# PK_MUV_L2.net
KiCad netlist of a schematic drawn in EAGLE
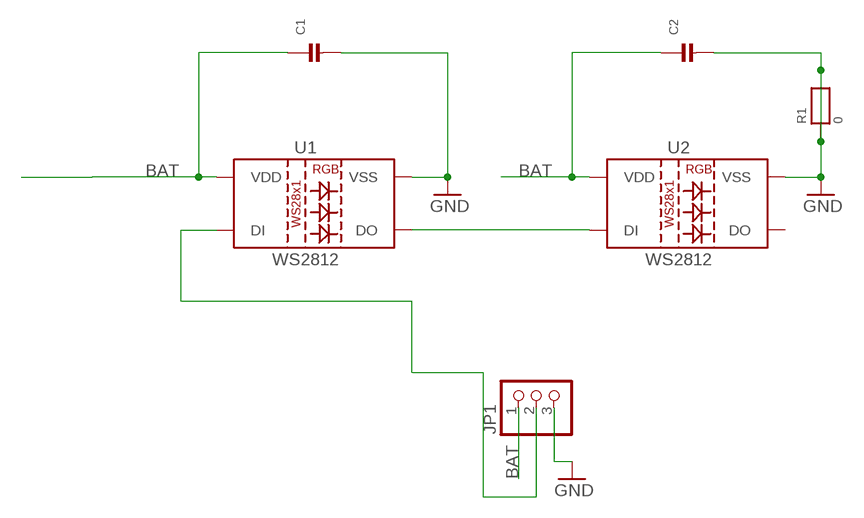
[diagram p0: schematic, sheet 1]

(export (version "E")
  (design (tool "Eeschema 10.0.6"))
  (components
    (comp (ref "C1")
      (value "CAP_CERAMIC1206")
      (footprint "eagle-import:1206")
      (libsource (lib "eagle-import") (part "CAP_CERAMIC1206"))
    )
    (comp (ref "C2")
      (value "CAP_CERAMIC1206")
      (footprint "eagle-import:1206")
      (libsource (lib "eagle-import") (part "CAP_CERAMIC1206"))
    )
    (comp (ref "JP1")
      (value "HEADER-1X3")
      (footprint "eagle-import:1X03_OVAL")
      (libsource (lib "eagle-import") (part "HEADER-1X3"))
    )
    (comp (ref "R1")
      (value "0")
      (footprint "eagle-import:1206")
      (libsource (lib "eagle-import") (part "RESISTOR1206"))
    )
    (comp (ref "U1")
      (value "WS2812")
      (footprint "eagle-import:LED-TRICOLOR-5050-IC")
      (libsource (lib "eagle-import") (part "WS2812{dblquote}"))
    )
    (comp (ref "U2")
      (value "WS2812")
      (footprint "eagle-import:LED-TRICOLOR-5050-IC")
      (libsource (lib "eagle-import") (part "WS2812{dblquote}"))
    )
  )
  (nets
    (net (code "1") (name "/BAT") (class "Default")
      (node (ref "C1") (pin "1") (pinfunction "P$1_1") (pintype "passive"))
      (node (ref "C2") (pin "1") (pinfunction "P$1_1") (pintype "passive"))
      (node (ref "JP1") (pin "1") (pinfunction "1_1") (pintype "passive"))
      (node (ref "U1") (pin "3") (pinfunction "VDD_3") (pintype "bidirectional"))
      (node (ref "U1") (pin "5") (pinfunction "VDD_5") (pintype "bidirectional"))
      (node (ref "U2") (pin "3") (pinfunction "VDD_3") (pintype "bidirectional"))
      (node (ref "U2") (pin "5") (pinfunction "VDD_5") (pintype "bidirectional"))
    )
    (net (code "2") (name "GND") (class "Default")
      (node (ref "C1") (pin "2") (pinfunction "P$2_2") (pintype "passive"))
      (node (ref "C2") (pin "2") (pinfunction "P$2_2") (pintype "passive"))
      (node (ref "JP1") (pin "3") (pinfunction "3_3") (pintype "passive"))
      (node (ref "R1") (pin "1") (pinfunction "1_1") (pintype "passive"))
      (node (ref "R1") (pin "2") (pinfunction "2_2") (pintype "passive"))
      (node (ref "U1") (pin "6") (pinfunction "VSS_6") (pintype "bidirectional"))
      (node (ref "U2") (pin "6") (pinfunction "VSS_6") (pintype "bidirectional"))
    )
    (net (code "3") (name "Net-(U1-DI)") (class "Default")
      (node (ref "JP1") (pin "2") (pinfunction "2_2") (pintype "passive"))
      (node (ref "U1") (pin "2") (pinfunction "DI_2") (pintype "bidirectional"))
    )
    (net (code "4") (name "Net-(U1-DO)") (class "Default")
      (node (ref "U1") (pin "1") (pinfunction "DO_1") (pintype "bidirectional"))
      (node (ref "U2") (pin "2") (pinfunction "DI_2") (pintype "bidirectional"))
    )
    (net (code "5") (name "unconnected-(U2-DO-Pad1)") (class "Default")
      (node (ref "U2") (pin "1") (pinfunction "DO_1") (pintype "bidirectional"))
    )
  )
)
